# Sheet1.net
KiCad netlist of a schematic drawn in Altium Designer
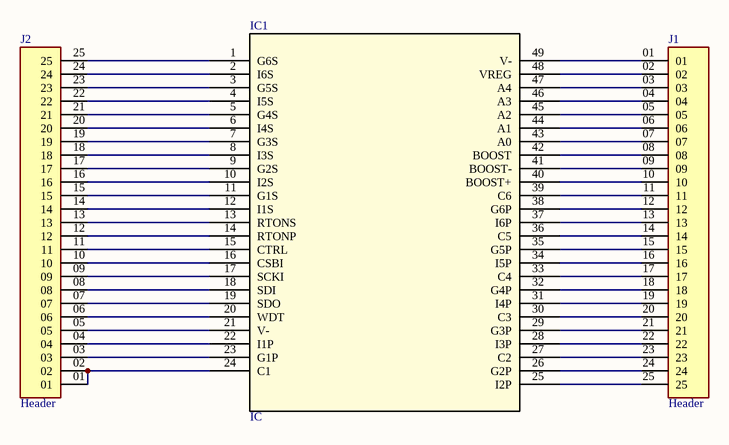
[diagram p0: Sheet1.SchDoc]

(export (version "E")
  (design (tool "Eeschema 10.0.6"))
  (components
    (comp (ref "IC1")
      (value "IC")
      (footprint "LQFP-48_LXE_LIT")
      (libsource (lib "Schlib1LTC3300") (part "IC"))
    )
    (comp (ref "J1")
      (value "Header")
      (footprint "SAMTEC_TS-125-G-A")
      (libsource (lib "Schlib1LTC3300") (part "Header"))
    )
    (comp (ref "J2") (value "Header") (footprint "SAMTEC_TS-125-G-A") (libsource (lib "") (part "Header_1")))
  )
  (nets
    (net (code "1") (name "Net-(IC1-A0)") (class "Default")
      (node (ref "IC1") (pin "43") (pinfunction "A0_43") (pintype "passive"))
      (node (ref "J1") (pin "07") (pinfunction "07_07") (pintype "passive"))
    )
    (net (code "2") (name "Net-(IC1-A1)") (class "Default")
      (node (ref "IC1") (pin "44") (pinfunction "A1_44") (pintype "passive"))
      (node (ref "J1") (pin "06") (pinfunction "06_06") (pintype "passive"))
    )
    (net (code "3") (name "Net-(IC1-A2)") (class "Default")
      (node (ref "IC1") (pin "45") (pinfunction "A2_45") (pintype "passive"))
      (node (ref "J1") (pin "05") (pinfunction "05_05") (pintype "passive"))
    )
    (net (code "4") (name "Net-(IC1-A3)") (class "Default")
      (node (ref "IC1") (pin "46") (pinfunction "A3_46") (pintype "passive"))
      (node (ref "J1") (pin "04") (pinfunction "04_04") (pintype "passive"))
    )
    (net (code "5") (name "Net-(IC1-A4)") (class "Default")
      (node (ref "IC1") (pin "47") (pinfunction "A4_47") (pintype "passive"))
      (node (ref "J1") (pin "03") (pinfunction "03_03") (pintype "passive"))
    )
    (net (code "6") (name "Net-(IC1-BOOST)") (class "Default")
      (node (ref "IC1") (pin "42") (pinfunction "BOOST_42") (pintype "passive"))
      (node (ref "J1") (pin "08") (pinfunction "08_08") (pintype "passive"))
    )
    (net (code "7") (name "Net-(IC1-BOOST+)") (class "Default")
      (node (ref "IC1") (pin "40") (pinfunction "BOOST+_40") (pintype "passive"))
      (node (ref "J1") (pin "10") (pinfunction "10_10") (pintype "passive"))
    )
    (net (code "8") (name "Net-(IC1-BOOST-)") (class "Default")
      (node (ref "IC1") (pin "41") (pinfunction "BOOST-_41") (pintype "passive"))
      (node (ref "J1") (pin "09") (pinfunction "09_09") (pintype "passive"))
    )
    (net (code "9") (name "Net-(IC1-C1)") (class "Default")
      (node (ref "IC1") (pin "24") (pinfunction "C1_24") (pintype "passive"))
      (node (ref "J2") (pin "01") (pinfunction "01_01") (pintype "passive"))
      (node (ref "J2") (pin "02") (pinfunction "02_02") (pintype "passive"))
    )
    (net (code "10") (name "Net-(IC1-C2)") (class "Default")
      (node (ref "IC1") (pin "27") (pinfunction "C2_27") (pintype "passive"))
      (node (ref "J1") (pin "23") (pinfunction "23_23") (pintype "passive"))
    )
    (net (code "11") (name "Net-(IC1-C3)") (class "Default")
      (node (ref "IC1") (pin "30") (pinfunction "C3_30") (pintype "passive"))
      (node (ref "J1") (pin "20") (pinfunction "20_20") (pintype "passive"))
    )
    (net (code "12") (name "Net-(IC1-C4)") (class "Default")
      (node (ref "IC1") (pin "33") (pinfunction "C4_33") (pintype "passive"))
      (node (ref "J1") (pin "17") (pinfunction "17_17") (pintype "passive"))
    )
    (net (code "13") (name "Net-(IC1-C5)") (class "Default")
      (node (ref "IC1") (pin "36") (pinfunction "C5_36") (pintype "passive"))
      (node (ref "J1") (pin "14") (pinfunction "14_14") (pintype "passive"))
    )
    (net (code "14") (name "Net-(IC1-C6)") (class "Default")
      (node (ref "IC1") (pin "39") (pinfunction "C6_39") (pintype "passive"))
      (node (ref "J1") (pin "11") (pinfunction "11_11") (pintype "passive"))
    )
    (net (code "15") (name "Net-(IC1-CSBI)") (class "Default")
      (node (ref "IC1") (pin "16") (pinfunction "CSBI_16") (pintype "passive"))
      (node (ref "J2") (pin "10") (pinfunction "10_10") (pintype "passive"))
    )
    (net (code "16") (name "Net-(IC1-CTRL)") (class "Default")
      (node (ref "IC1") (pin "15") (pinfunction "CTRL_15") (pintype "passive"))
      (node (ref "J2") (pin "11") (pinfunction "11_11") (pintype "passive"))
    )
    (net (code "17") (name "Net-(IC1-G1P)") (class "Default")
      (node (ref "IC1") (pin "23") (pinfunction "G1P_23") (pintype "passive"))
      (node (ref "J2") (pin "03") (pinfunction "03_03") (pintype "passive"))
    )
    (net (code "18") (name "Net-(IC1-G1S)") (class "Default")
      (node (ref "IC1") (pin "11") (pinfunction "G1S_11") (pintype "passive"))
      (node (ref "J2") (pin "15") (pinfunction "15_15") (pintype "passive"))
    )
    (net (code "19") (name "Net-(IC1-G2P)") (class "Default")
      (node (ref "IC1") (pin "26") (pinfunction "G2P_26") (pintype "passive"))
      (node (ref "J1") (pin "24") (pinfunction "24_24") (pintype "passive"))
    )
    (net (code "20") (name "Net-(IC1-G2S)") (class "Default")
      (node (ref "IC1") (pin "9") (pinfunction "G2S_9") (pintype "passive"))
      (node (ref "J2") (pin "17") (pinfunction "17_17") (pintype "passive"))
    )
    (net (code "21") (name "Net-(IC1-G3P)") (class "Default")
      (node (ref "IC1") (pin "29") (pinfunction "G3P_29") (pintype "passive"))
      (node (ref "J1") (pin "21") (pinfunction "21_21") (pintype "passive"))
    )
    (net (code "22") (name "Net-(IC1-G3S)") (class "Default")
      (node (ref "IC1") (pin "7") (pinfunction "G3S_7") (pintype "passive"))
      (node (ref "J2") (pin "19") (pinfunction "19_19") (pintype "passive"))
    )
    (net (code "23") (name "Net-(IC1-G4P)") (class "Default")
      (node (ref "IC1") (pin "32") (pinfunction "G4P_32") (pintype "passive"))
      (node (ref "J1") (pin "18") (pinfunction "18_18") (pintype "passive"))
    )
    (net (code "24") (name "Net-(IC1-G4S)") (class "Default")
      (node (ref "IC1") (pin "5") (pinfunction "G4S_5") (pintype "passive"))
      (node (ref "J2") (pin "21") (pinfunction "21_21") (pintype "passive"))
    )
    (net (code "25") (name "Net-(IC1-G5P)") (class "Default")
      (node (ref "IC1") (pin "35") (pinfunction "G5P_35") (pintype "passive"))
      (node (ref "J1") (pin "15") (pinfunction "15_15") (pintype "passive"))
    )
    (net (code "26") (name "Net-(IC1-G5S)") (class "Default")
      (node (ref "IC1") (pin "3") (pinfunction "G5S_3") (pintype "passive"))
      (node (ref "J2") (pin "23") (pinfunction "23_23") (pintype "passive"))
    )
    (net (code "27") (name "Net-(IC1-G6P)") (class "Default")
      (node (ref "IC1") (pin "38") (pinfunction "G6P_38") (pintype "passive"))
      (node (ref "J1") (pin "12") (pinfunction "12_12") (pintype "passive"))
    )
    (net (code "28") (name "Net-(IC1-G6S)") (class "Default")
      (node (ref "IC1") (pin "1") (pinfunction "G6S_1") (pintype "passive"))
      (node (ref "J2") (pin "25") (pinfunction "25_25") (pintype "passive"))
    )
    (net (code "29") (name "Net-(IC1-I1P)") (class "Default")
      (node (ref "IC1") (pin "22") (pinfunction "I1P_22") (pintype "passive"))
      (node (ref "J2") (pin "04") (pinfunction "04_04") (pintype "passive"))
    )
    (net (code "30") (name "Net-(IC1-I1S)") (class "Default")
      (node (ref "IC1") (pin "12") (pinfunction "I1S_12") (pintype "passive"))
      (node (ref "J2") (pin "14") (pinfunction "14_14") (pintype "passive"))
    )
    (net (code "31") (name "Net-(IC1-I2P)") (class "Default")
      (node (ref "IC1") (pin "25") (pinfunction "I2P_25") (pintype "passive"))
      (node (ref "J1") (pin "25") (pinfunction "25_25") (pintype "passive"))
    )
    (net (code "32") (name "Net-(IC1-I2S)") (class "Default")
      (node (ref "IC1") (pin "10") (pinfunction "I2S_10") (pintype "passive"))
      (node (ref "J2") (pin "16") (pinfunction "16_16") (pintype "passive"))
    )
    (net (code "33") (name "Net-(IC1-I3P)") (class "Default")
      (node (ref "IC1") (pin "28") (pinfunction "I3P_28") (pintype "passive"))
      (node (ref "J1") (pin "22") (pinfunction "22_22") (pintype "passive"))
    )
    (net (code "34") (name "Net-(IC1-I3S)") (class "Default")
      (node (ref "IC1") (pin "8") (pinfunction "I3S_8") (pintype "passive"))
      (node (ref "J2") (pin "18") (pinfunction "18_18") (pintype "passive"))
    )
    (net (code "35") (name "Net-(IC1-I4P)") (class "Default")
      (node (ref "IC1") (pin "31") (pinfunction "I4P_31") (pintype "passive"))
      (node (ref "J1") (pin "19") (pinfunction "19_19") (pintype "passive"))
    )
    (net (code "36") (name "Net-(IC1-I4S)") (class "Default")
      (node (ref "IC1") (pin "6") (pinfunction "I4S_6") (pintype "passive"))
      (node (ref "J2") (pin "20") (pinfunction "20_20") (pintype "passive"))
    )
    (net (code "37") (name "Net-(IC1-I5P)") (class "Default")
      (node (ref "IC1") (pin "34") (pinfunction "I5P_34") (pintype "passive"))
      (node (ref "J1") (pin "16") (pinfunction "16_16") (pintype "passive"))
    )
    (net (code "38") (name "Net-(IC1-I5S)") (class "Default")
      (node (ref "IC1") (pin "4") (pinfunction "I5S_4") (pintype "passive"))
      (node (ref "J2") (pin "22") (pinfunction "22_22") (pintype "passive"))
    )
    (net (code "39") (name "Net-(IC1-I6P)") (class "Default")
      (node (ref "IC1") (pin "37") (pinfunction "I6P_37") (pintype "passive"))
      (node (ref "J1") (pin "13") (pinfunction "13_13") (pintype "passive"))
    )
    (net (code "40") (name "Net-(IC1-I6S)") (class "Default")
      (node (ref "IC1") (pin "2") (pinfunction "I6S_2") (pintype "passive"))
      (node (ref "J2") (pin "24") (pinfunction "24_24") (pintype "passive"))
    )
    (net (code "41") (name "Net-(IC1-RTONP)") (class "Default")
      (node (ref "IC1") (pin "14") (pinfunction "RTONP_14") (pintype "passive"))
      (node (ref "J2") (pin "12") (pinfunction "12_12") (pintype "passive"))
    )
    (net (code "42") (name "Net-(IC1-RTONS)") (class "Default")
      (node (ref "IC1") (pin "13") (pinfunction "RTONS_13") (pintype "passive"))
      (node (ref "J2") (pin "13") (pinfunction "13_13") (pintype "passive"))
    )
    (net (code "43") (name "Net-(IC1-SCKI)") (class "Default")
      (node (ref "IC1") (pin "17") (pinfunction "SCKI_17") (pintype "passive"))
      (node (ref "J2") (pin "09") (pinfunction "09_09") (pintype "passive"))
    )
    (net (code "44") (name "Net-(IC1-SDI)") (class "Default")
      (node (ref "IC1") (pin "18") (pinfunction "SDI_18") (pintype "passive"))
      (node (ref "J2") (pin "08") (pinfunction "08_08") (pintype "passive"))
    )
    (net (code "45") (name "Net-(IC1-SDO)") (class "Default")
      (node (ref "IC1") (pin "19") (pinfunction "SDO_19") (pintype "passive"))
      (node (ref "J2") (pin "07") (pinfunction "07_07") (pintype "passive"))
    )
    (net (code "46") (name "Net-(IC1-V--Pad21)") (class "Default")
      (node (ref "IC1") (pin "21") (pinfunction "V-_21") (pintype "power_in"))
      (node (ref "J2") (pin "05") (pinfunction "05_05") (pintype "passive"))
    )
    (net (code "47") (name "Net-(IC1-V--Pad49)") (class "Default")
      (node (ref "IC1") (pin "49") (pinfunction "V-_49") (pintype "power_in"))
      (node (ref "J1") (pin "01") (pinfunction "01_01") (pintype "passive"))
    )
    (net (code "48") (name "Net-(IC1-VREG)") (class "Default")
      (node (ref "IC1") (pin "48") (pinfunction "VREG_48") (pintype "passive"))
      (node (ref "J1") (pin "02") (pinfunction "02_02") (pintype "passive"))
    )
    (net (code "49") (name "Net-(IC1-WDT)") (class "Default")
      (node (ref "IC1") (pin "20") (pinfunction "WDT_20") (pintype "passive"))
      (node (ref "J2") (pin "06") (pinfunction "06_06") (pintype "passive"))
    )
  )
)
